# OPA381.net
KiCad netlist of a schematic drawn in EAGLE
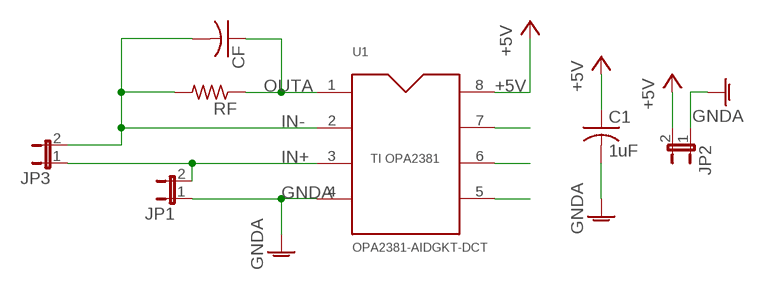
[diagram p0: schematic, sheet 1]

(export (version "E")
  (design (tool "Eeschema 10.0.6"))
  (components
    (comp (ref "C1")
      (value "1uF")
      (footprint "eagle-import:C0603")
      (libsource (lib "eagle-import") (part "C-USC0603"))
    )
    (comp (ref "CF")
      (value "C-USC0603")
      (footprint "eagle-import:C0603")
      (libsource (lib "eagle-import") (part "C-USC0603"))
    )
    (comp (ref "JP1")
      (value "JP1E")
      (footprint "eagle-import:JP1")
      (libsource (lib "eagle-import") (part "JP1E"))
    )
    (comp (ref "JP2")
      (value "JP1E")
      (footprint "eagle-import:JP1")
      (libsource (lib "eagle-import") (part "JP1E"))
    )
    (comp (ref "JP3")
      (value "JP1E")
      (footprint "eagle-import:JP1")
      (libsource (lib "eagle-import") (part "JP1E"))
    )
    (comp (ref "RF")
      (value "R-US_R0603")
      (footprint "eagle-import:R0603")
      (libsource (lib "eagle-import") (part "R-US_R0603"))
    )
    (comp (ref "U1")
      (value "OPA2381-AIDGKT-DCT")
      (footprint "eagle-import:SSOP8")
      (libsource (lib "eagle-import") (part "OPA2381-AIDGKT-DCT"))
    )
  )
  (nets
    (net (code "1") (name "+5V") (class "Default")
      (node (ref "C1") (pin "1") (pinfunction "1_1") (pintype "passive"))
      (node (ref "JP2") (pin "2") (pinfunction "2_2") (pintype "passive"))
      (node (ref "U1") (pin "8") (pinfunction "P$8_8") (pintype "bidirectional"))
    )
    (net (code "2") (name "/IN+") (class "Default")
      (node (ref "JP1") (pin "2") (pinfunction "2_2") (pintype "passive"))
      (node (ref "JP3") (pin "1") (pinfunction "1_1") (pintype "passive"))
      (node (ref "U1") (pin "3") (pinfunction "P$3_3") (pintype "bidirectional"))
    )
    (net (code "3") (name "/IN-") (class "Default")
      (node (ref "CF") (pin "2") (pinfunction "2_2") (pintype "passive"))
      (node (ref "JP3") (pin "2") (pinfunction "2_2") (pintype "passive"))
      (node (ref "RF") (pin "2") (pinfunction "2_2") (pintype "passive"))
      (node (ref "U1") (pin "2") (pinfunction "P$2_2") (pintype "bidirectional"))
    )
    (net (code "4") (name "/OUTA") (class "Default")
      (node (ref "CF") (pin "1") (pinfunction "1_1") (pintype "passive"))
      (node (ref "RF") (pin "1") (pinfunction "1_1") (pintype "passive"))
      (node (ref "U1") (pin "1") (pinfunction "P$1_1") (pintype "bidirectional"))
    )
    (net (code "5") (name "GNDA") (class "Default")
      (node (ref "C1") (pin "2") (pinfunction "2_2") (pintype "passive"))
      (node (ref "JP1") (pin "1") (pinfunction "1_1") (pintype "passive"))
      (node (ref "JP2") (pin "1") (pinfunction "1_1") (pintype "passive"))
      (node (ref "U1") (pin "4") (pinfunction "P$4_4") (pintype "bidirectional"))
    )
    (net (code "6") (name "unconnected-(U1-P$5-Pad5)") (class "Default")
      (node (ref "U1") (pin "5") (pinfunction "P$5_5") (pintype "bidirectional"))
    )
    (net (code "7") (name "unconnected-(U1-P$6-Pad6)") (class "Default")
      (node (ref "U1") (pin "6") (pinfunction "P$6_6") (pintype "bidirectional"))
    )
    (net (code "8") (name "unconnected-(U1-P$7-Pad7)") (class "Default")
      (node (ref "U1") (pin "7") (pinfunction "P$7_7") (pintype "bidirectional"))
    )
  )
)
